# v2_0.net
KiCad netlist of a schematic drawn in Altium Designer
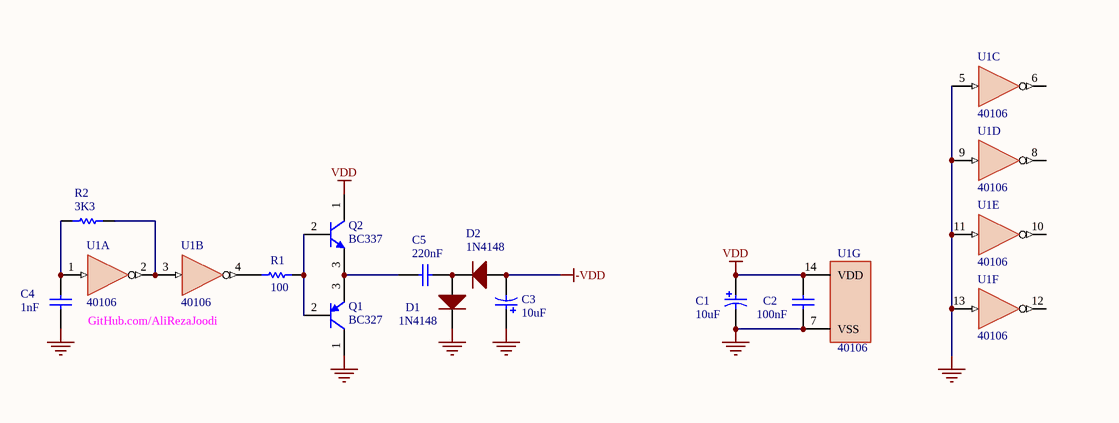
[diagram p0: v2.0.SchDoc]

(export (version "E")
  (design (tool "Eeschema 10.0.6"))
  (components
    (comp (ref "C1")
      (value "10uF")
      (footprint "THD_P2.54/D6/H11")
      (description "Capacitor, Electrolytic, 25V, 20%")
      (fields (field (name "1_PART NUMBER") "ESK227M025AG3EA"))
      (libsource (lib "General") (part "Capacitor_Electrolytic"))
    )
    (comp (ref "C2")
      (value "100nF")
      (footprint "THD_P2.54/D5/T2")
      (description "Capacitor, Ceramic Multilayer, 25V, 10%")
      (libsource (lib "General") (part "Capacitor_Ceramic"))
    )
    (comp (ref "C3")
      (value "10uF")
      (footprint "THD_P2.54/D6/H11")
      (description "Capacitor, Electrolytic, 25V, 20%")
      (fields (field (name "1_PART NUMBER") "ESK227M025AG3EA"))
      (libsource (lib "General") (part "Capacitor_Electrolytic"))
    )
    (comp (ref "C4")
      (value "1nF")
      (footprint "THD_P2.54/D5/T2")
      (description "Capacitor, Ceramic Multilayer, 25V, 10%")
      (libsource (lib "General") (part "Capacitor_Ceramic"))
    )
    (comp (ref "C5")
      (value "220nF")
      (footprint "THD_P5.08/D4.2/T2")
      (description "Capacitor, Ceramic Multilayer, 25V, 10%")
      (libsource (lib "General") (part "Capacitor_Ceramic"))
    )
    (comp (ref "D1")
      (value "1N4148")
      (footprint "THD_AXIAL0.3_DO-35")
      (description "Diode")
      (fields (field (name "1_PART NUMBER") "1N4148UR-1"))
      (libsource (lib "General") (part "Diode_2Form"))
    )
    (comp (ref "D2")
      (value "1N4148")
      (footprint "THD_AXIAL0.3_DO-35")
      (description "Diode")
      (fields (field (name "1_PART NUMBER") "1N4148UR-1"))
      (libsource (lib "General") (part "Diode_2Form"))
    )
    (comp (ref "Q1")
      (value "BC327")
      (footprint "TO92_3Pin")
      (description "Transistor, BJT, PNP")
      (libsource (lib "General") (part "Transistor_BJT_PNP_cbe"))
    )
    (comp (ref "Q2")
      (value "BC337")
      (footprint "TO92_3Pin")
      (description "Transistor, BJT, NPN")
      (libsource (lib "General") (part "Transistor_BJT_NPN_cbe"))
    )
    (comp (ref "R1")
      (value "100")
      (footprint "THD_AXIAL0.4")
      (description "Resistor, 1/4W, 5%")
      (libsource (lib "General") (part "Resistor"))
    )
    (comp (ref "R2")
      (value "3K3")
      (footprint "THD_AXIAL0.4_VER")
      (description "Resistor, 1/4W, 5%")
      (libsource (lib "General") (part "Resistor"))
    )
    (comp (ref "U1")
      (value "40106")
      (footprint "DIP_14")
      (description "Hex inverting Schmitt trigger")
      (fields (field (name "1_PART NUMBER") "CD40106BM96"))
      (libsource (lib "IC") (part "40106"))
    )
  )
  (nets
    (net (code "1") (name "-VDD") (class "Default")
      (node (ref "C3") (pin "2") (pinfunction "2_2") (pintype "passive"))
      (node (ref "D2") (pin "1") (pinfunction "A_1") (pintype "passive"))
    )
    (net (code "2") (name "GND") (class "Default")
      (node (ref "C1") (pin "2") (pinfunction "2_2") (pintype "passive"))
      (node (ref "C2") (pin "1") (pinfunction "1_1") (pintype "passive"))
      (node (ref "C3") (pin "1") (pinfunction "1_1") (pintype "passive"))
      (node (ref "C4") (pin "1") (pinfunction "1_1") (pintype "passive"))
      (node (ref "D1") (pin "2") (pinfunction "K_2") (pintype "passive"))
      (node (ref "Q1") (pin "1") (pinfunction "C_1") (pintype "passive"))
      (node (ref "U1") (pin "11") (pinfunction "I_11") (pintype "input"))
      (node (ref "U1") (pin "13") (pinfunction "I_13") (pintype "input"))
      (node (ref "U1") (pin "5") (pinfunction "I_5") (pintype "input"))
      (node (ref "U1") (pin "7") (pinfunction "VSS_7") (pintype "power_in"))
      (node (ref "U1") (pin "9") (pinfunction "I_9") (pintype "input"))
    )
    (net (code "3") (name "Net-(D1-A)") (class "Default")
      (node (ref "C5") (pin "1") (pinfunction "1_1") (pintype "passive"))
      (node (ref "D1") (pin "1") (pinfunction "A_1") (pintype "passive"))
      (node (ref "D2") (pin "2") (pinfunction "K_2") (pintype "passive"))
    )
    (net (code "4") (name "Net-(Q1-B)") (class "Default")
      (node (ref "Q1") (pin "2") (pinfunction "B_2") (pintype "passive"))
      (node (ref "Q2") (pin "2") (pinfunction "B_2") (pintype "passive"))
      (node (ref "R1") (pin "1") (pinfunction "1_1") (pintype "passive"))
    )
    (net (code "5") (name "Net-(Q1-E)") (class "Default")
      (node (ref "C5") (pin "2") (pinfunction "2_2") (pintype "passive"))
      (node (ref "Q1") (pin "3") (pinfunction "E_3") (pintype "passive"))
      (node (ref "Q2") (pin "3") (pinfunction "E_3") (pintype "passive"))
    )
    (net (code "6") (name "Net-(U1A-I)") (class "Default")
      (node (ref "C4") (pin "2") (pinfunction "2_2") (pintype "passive"))
      (node (ref "R2") (pin "2") (pinfunction "2_2") (pintype "passive"))
      (node (ref "U1") (pin "1") (pinfunction "I_1") (pintype "input"))
    )
    (net (code "7") (name "Net-(U1A-~{O})") (class "Default")
      (node (ref "R2") (pin "1") (pinfunction "1_1") (pintype "passive"))
      (node (ref "U1") (pin "2") (pinfunction "~{O}_2") (pintype "output"))
      (node (ref "U1") (pin "3") (pinfunction "I_3") (pintype "input"))
    )
    (net (code "8") (name "Net-(U1B-~{O})") (class "Default")
      (node (ref "R1") (pin "2") (pinfunction "2_2") (pintype "passive"))
      (node (ref "U1") (pin "4") (pinfunction "~{O}_4") (pintype "output"))
    )
    (net (code "9") (name "VDD") (class "Default")
      (node (ref "C1") (pin "1") (pinfunction "1_1") (pintype "passive"))
      (node (ref "C2") (pin "2") (pinfunction "2_2") (pintype "passive"))
      (node (ref "Q2") (pin "1") (pinfunction "C_1") (pintype "passive"))
      (node (ref "U1") (pin "14") (pinfunction "VDD_14") (pintype "passive"))
    )
    (net (code "10") (name "unconnected-(U1C-~{O}-Pad6)") (class "Default")
      (node (ref "U1") (pin "6") (pinfunction "~{O}_6") (pintype "output"))
    )
    (net (code "11") (name "unconnected-(U1D-~{O}-Pad8)") (class "Default")
      (node (ref "U1") (pin "8") (pinfunction "~{O}_8") (pintype "output"))
    )
    (net (code "12") (name "unconnected-(U1E-~{O}-Pad10)") (class "Default")
      (node (ref "U1") (pin "10") (pinfunction "~{O}_10") (pintype "output"))
    )
    (net (code "13") (name "unconnected-(U1F-~{O}-Pad12)") (class "Default")
      (node (ref "U1") (pin "12") (pinfunction "~{O}_12") (pintype "output"))
    )
  )
)
